# Adafruit_Metro_ESP32-S2_rev_C.net
KiCad netlist of a schematic drawn in EAGLE
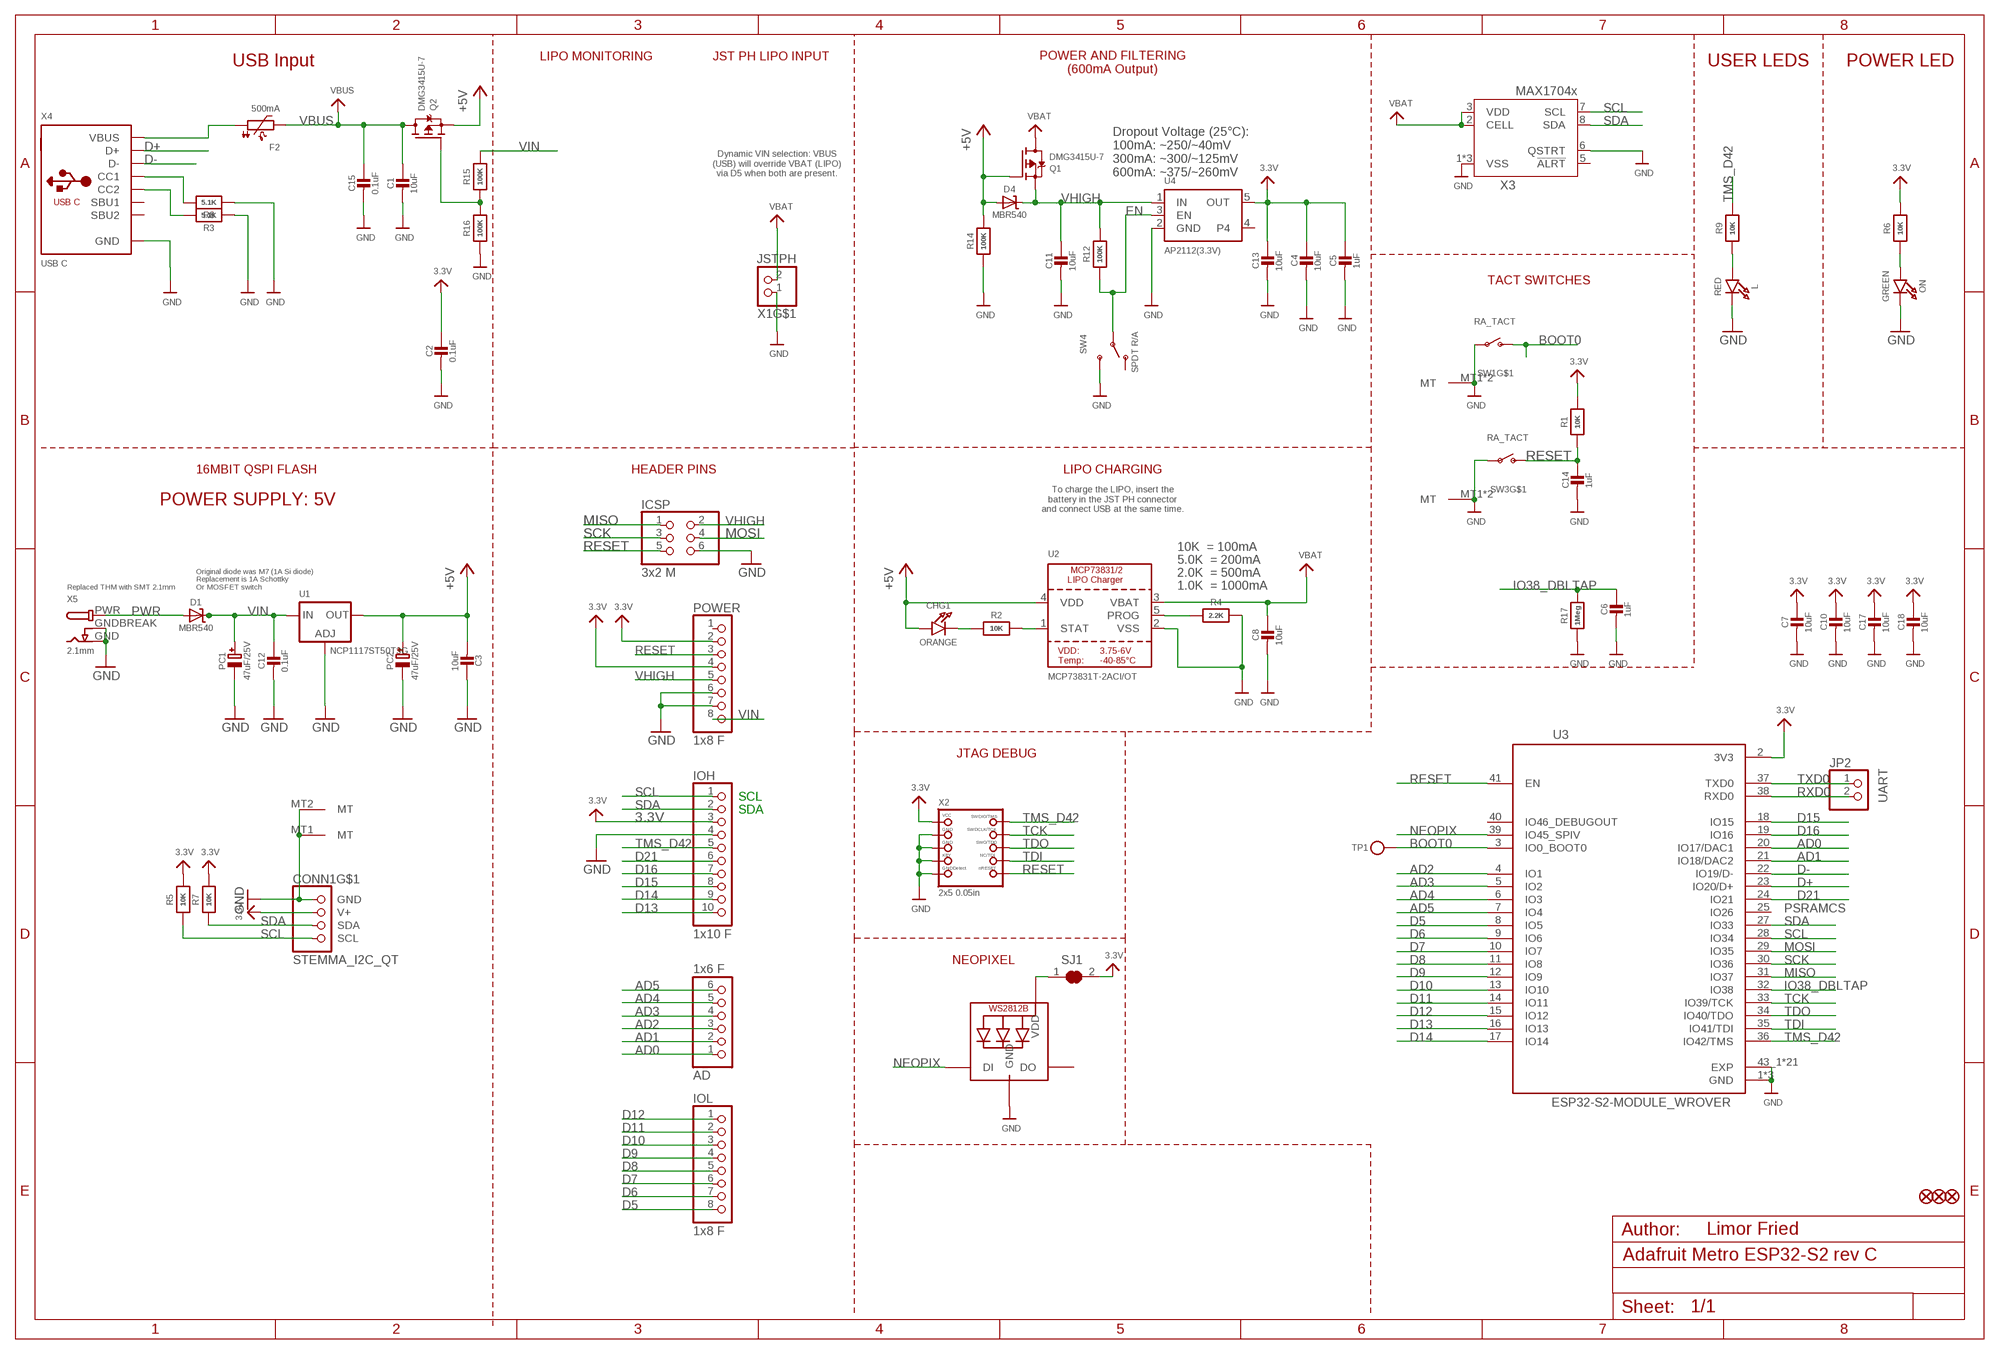
[diagram p0: schematic, sheet 1]

(export (version "E")
  (design (tool "Eeschema 10.0.6"))
  (components
    (comp (ref "AD")
      (value "1x6 F")
      (footprint "eagle-import:1X06_OVALWAVE")
      (libsource (lib "eagle-import") (part "HEADER-1X6OVALWAVE"))
    )
    (comp (ref "C1")
      (value "10uF")
      (footprint "eagle-import:0805-NO")
      (libsource (lib "eagle-import") (part "CAP_CERAMIC0805-NOOUTLINE"))
    )
    (comp (ref "C2")
      (value "0.1uF")
      (footprint "eagle-import:0603-NO")
      (libsource (lib "eagle-import") (part "CAP_CERAMIC0603_NO"))
    )
    (comp (ref "C3")
      (value "10uF")
      (footprint "eagle-import:0805-NO")
      (libsource (lib "eagle-import") (part "CAP_CERAMIC0805-NOOUTLINE"))
    )
    (comp (ref "C4")
      (value "10uF")
      (footprint "eagle-import:0805-NO")
      (libsource (lib "eagle-import") (part "CAP_CERAMIC0805-NOOUTLINE"))
    )
    (comp (ref "C5")
      (value "1uF")
      (footprint "eagle-import:0603-NO")
      (libsource (lib "eagle-import") (part "CAP_CERAMIC0603_NO"))
    )
    (comp (ref "C6")
      (value "1uF")
      (footprint "eagle-import:0603-NO")
      (libsource (lib "eagle-import") (part "CAP_CERAMIC0603_NO"))
    )
    (comp (ref "C7")
      (value "10uF")
      (footprint "eagle-import:0805-NO")
      (libsource (lib "eagle-import") (part "CAP_CERAMIC0805-NOOUTLINE"))
    )
    (comp (ref "C8")
      (value "10uF")
      (footprint "eagle-import:0805-NO")
      (libsource (lib "eagle-import") (part "CAP_CERAMIC0805-NOOUTLINE"))
    )
    (comp (ref "C10")
      (value "10uF")
      (footprint "eagle-import:0805-NO")
      (libsource (lib "eagle-import") (part "CAP_CERAMIC0805-NOOUTLINE"))
    )
    (comp (ref "C11")
      (value "10uF")
      (footprint "eagle-import:0805-NO")
      (libsource (lib "eagle-import") (part "CAP_CERAMIC0805-NOOUTLINE"))
    )
    (comp (ref "C12")
      (value "0.1uF")
      (footprint "eagle-import:0603-NO")
      (libsource (lib "eagle-import") (part "CAP_CERAMIC0603_NO"))
    )
    (comp (ref "C13")
      (value "10uF")
      (footprint "eagle-import:0805-NO")
      (libsource (lib "eagle-import") (part "CAP_CERAMIC0805-NOOUTLINE"))
    )
    (comp (ref "C14")
      (value "1uF")
      (footprint "eagle-import:0603-NO")
      (libsource (lib "eagle-import") (part "CAP_CERAMIC0603_NO"))
    )
    (comp (ref "C15")
      (value "0.1uF")
      (footprint "eagle-import:0603-NO")
      (libsource (lib "eagle-import") (part "CAP_CERAMIC0603_NO"))
    )
    (comp (ref "C17")
      (value "10uF")
      (footprint "eagle-import:0805-NO")
      (libsource (lib "eagle-import") (part "CAP_CERAMIC0805-NOOUTLINE"))
    )
    (comp (ref "C18")
      (value "10uF")
      (footprint "eagle-import:0805-NO")
      (libsource (lib "eagle-import") (part "CAP_CERAMIC0805-NOOUTLINE"))
    )
    (comp (ref "CHG1")
      (value "ORANGE")
      (footprint "eagle-import:CHIPLED_0603_NOOUTLINE")
      (libsource (lib "eagle-import") (part "LED0603_NOOUTLINE"))
    )
    (comp (ref "CONN1")
      (value "STEMMA_I2C_QT")
      (footprint "eagle-import:JST_SH4")
      (libsource (lib "eagle-import") (part "STEMMA_I2C_QT"))
    )
    (comp (ref "D1")
      (value "MBR540")
      (footprint "eagle-import:SOD-123")
      (libsource (lib "eagle-import") (part "DIODE-SCHOTTKYSOD-123"))
    )
    (comp (ref "D4")
      (value "MBR540")
      (footprint "eagle-import:SOD-123")
      (libsource (lib "eagle-import") (part "DIODE-SCHOTTKYSOD-123"))
    )
    (comp (ref "F2")
      (value "500mA")
      (footprint "eagle-import:1206")
      (libsource (lib "eagle-import") (part "PTC1206"))
    )
    (comp (ref "FD1")
      (value "FIDUCIAL_1MM")
      (footprint "eagle-import:FIDUCIAL_1MM")
      (libsource (lib "eagle-import") (part "FIDUCIAL_1MM"))
    )
    (comp (ref "FD2")
      (value "FIDUCIAL_1MM")
      (footprint "eagle-import:FIDUCIAL_1MM")
      (libsource (lib "eagle-import") (part "FIDUCIAL_1MM"))
    )
    (comp (ref "FD3")
      (value "FIDUCIAL_1MM")
      (footprint "eagle-import:FIDUCIAL_1MM")
      (libsource (lib "eagle-import") (part "FIDUCIAL_1MM"))
    )
    (comp (ref "ICSP")
      (value "3x2 M")
      (footprint "eagle-import:2X03_ROUND_70MIL")
      (libsource (lib "eagle-import") (part "HEADER-2X3"))
    )
    (comp (ref "IOH")
      (value "1x10 F")
      (footprint "eagle-import:1X10_OVALWAVE")
      (libsource (lib "eagle-import") (part "HEADER-1X10OVALWAVE"))
    )
    (comp (ref "IOL")
      (value "1x8 F")
      (footprint "eagle-import:1X08_OVALWAVE")
      (libsource (lib "eagle-import") (part "HEADER-1X8OVALWAVE"))
    )
    (comp (ref "JP2")
      (value "UART")
      (footprint "eagle-import:1X02_ROUND")
      (libsource (lib "eagle-import") (part "HEADER-1X2ROUND"))
    )
    (comp (ref "L")
      (value "RED")
      (footprint "eagle-import:CHIPLED_0603_NOOUTLINE")
      (libsource (lib "eagle-import") (part "LED0603_NOOUTLINE"))
    )
    (comp (ref "LED1")
      (value "WS2812B_3535FULL")
      (footprint "eagle-import:LED3535_FULLPADS")
      (libsource (lib "eagle-import") (part "WS2812B_3535FULL"))
    )
    (comp (ref "ON")
      (value "GREEN")
      (footprint "eagle-import:CHIPLED_0603_NOOUTLINE")
      (libsource (lib "eagle-import") (part "LED0603_NOOUTLINE"))
    )
    (comp (ref "PC1")
      (value "47uF/25V")
      (footprint "eagle-import:PANASONIC_D")
      (libsource (lib "eagle-import") (part "CAP_ELECTROLYTICPANASONIC_D"))
    )
    (comp (ref "PC2")
      (value "47uF/25V")
      (footprint "eagle-import:PANASONIC_D")
      (libsource (lib "eagle-import") (part "CAP_ELECTROLYTICPANASONIC_D"))
    )
    (comp (ref "POWER")
      (value "1x8 F")
      (footprint "eagle-import:1X08_OVALWAVE")
      (libsource (lib "eagle-import") (part "HEADER-1X8OVALWAVE"))
    )
    (comp (ref "Q1")
      (value "DMG3415U-7")
      (footprint "eagle-import:SOT23-R")
      (libsource (lib "eagle-import") (part "MOSFET-P"))
    )
    (comp (ref "Q2")
      (value "DMG3415U-7")
      (footprint "eagle-import:SOT23-R")
      (libsource (lib "eagle-import") (part "MOSFET-P"))
    )
    (comp (ref "R1")
      (value "10K")
      (footprint "eagle-import:0603-NO")
      (libsource (lib "eagle-import") (part "RESISTOR_0603_NOOUT"))
    )
    (comp (ref "R2")
      (value "10K")
      (footprint "eagle-import:0603-NO")
      (libsource (lib "eagle-import") (part "RESISTOR_0603_NOOUT"))
    )
    (comp (ref "R3")
      (value "5.1K")
      (footprint "eagle-import:0603-NO")
      (libsource (lib "eagle-import") (part "RESISTOR_0603_NOOUT"))
    )
    (comp (ref "R4")
      (value "2.2K")
      (footprint "eagle-import:0603-NO")
      (libsource (lib "eagle-import") (part "RESISTOR_0603_NOOUT"))
    )
    (comp (ref "R5")
      (value "10K")
      (footprint "eagle-import:0603-NO")
      (libsource (lib "eagle-import") (part "RESISTOR_0603_NOOUT"))
    )
    (comp (ref "R6")
      (value "10K")
      (footprint "eagle-import:0603-NO")
      (libsource (lib "eagle-import") (part "RESISTOR_0603_NOOUT"))
    )
    (comp (ref "R7")
      (value "10K")
      (footprint "eagle-import:0603-NO")
      (libsource (lib "eagle-import") (part "RESISTOR_0603_NOOUT"))
    )
    (comp (ref "R8")
      (value "5.1K")
      (footprint "eagle-import:0603-NO")
      (libsource (lib "eagle-import") (part "RESISTOR_0603_NOOUT"))
    )
    (comp (ref "R9")
      (value "10K")
      (footprint "eagle-import:0603-NO")
      (libsource (lib "eagle-import") (part "RESISTOR_0603_NOOUT"))
    )
    (comp (ref "R12")
      (value "100K")
      (footprint "eagle-import:0603-NO")
      (libsource (lib "eagle-import") (part "RESISTOR_0603_NOOUT"))
    )
    (comp (ref "R14")
      (value "100K")
      (footprint "eagle-import:0603-NO")
      (libsource (lib "eagle-import") (part "RESISTOR_0603_NOOUT"))
    )
    (comp (ref "R15")
      (value "100K")
      (footprint "eagle-import:0603-NO")
      (libsource (lib "eagle-import") (part "RESISTOR_0603_NOOUT"))
    )
    (comp (ref "R16")
      (value "100K")
      (footprint "eagle-import:0603-NO")
      (libsource (lib "eagle-import") (part "RESISTOR_0603_NOOUT"))
    )
    (comp (ref "R17")
      (value "1Meg")
      (footprint "eagle-import:0603-NO")
      (libsource (lib "eagle-import") (part "RESISTOR_0603_NOOUT"))
    )
    (comp (ref "SJ1")
      (value "SOLDERJUMPER_CLOSED")
      (footprint "eagle-import:SOLDERJUMPER_CLOSEDWIRE")
      (libsource (lib "eagle-import") (part "SOLDERJUMPER_CLOSED"))
    )
    (comp (ref "SW1")
      (value "RA_TACT")
      (footprint "eagle-import:SPST_TACTILE_RA")
      (libsource (lib "eagle-import") (part "SWITCH_SPST_MNT_TACT_RA"))
    )
    (comp (ref "SW3")
      (value "RA_TACT")
      (footprint "eagle-import:SPST_TACTILE_RA")
      (libsource (lib "eagle-import") (part "SWITCH_SPST_MNT_TACT_RA"))
    )
    (comp (ref "SW4")
      (value "SPDT R/A")
      (footprint "eagle-import:SPDT_SMT_SSSS811101")
      (libsource (lib "eagle-import") (part "SWITCH_SPDT"))
    )
    (comp (ref "TP1")
      (value "TESTPOINTROUND1.5MMNO")
      (footprint "eagle-import:TESTPOINT_ROUND_1.5MM_NO")
      (libsource (lib "eagle-import") (part "TESTPOINTROUND1.5MMNO"))
    )
    (comp (ref "U1")
      (value "NCP1117ST50T3G")
      (footprint "eagle-import:SOT223-R")
      (libsource (lib "eagle-import") (part "LM1117SOT223-REFLOW"))
    )
    (comp (ref "U2")
      (value "MCP73831T-2ACI/OT")
      (footprint "eagle-import:SOT23-5")
      (libsource (lib "eagle-import") (part "MCP73831/2"))
    )
    (comp (ref "U3")
      (value "ESP32-S2-MODULE_WROVER")
      (footprint "eagle-import:MODULE_ESP32-S2-WROVER")
      (fields (field (name "MF") "Espressif Systems") (field (name "MP") "ESP32-S2-WROVER"))
      (libsource (lib "eagle-import") (part "ESP32-S2-MODULE_WROVER"))
    )
    (comp (ref "U4")
      (value "AP2112(3.3V)")
      (footprint "eagle-import:SOT23-5")
      (fields (field (name "JLC_ROTATION") "0"))
      (libsource (lib "eagle-import") (part "VREG_SOT23-5"))
    )
    (comp (ref "X1")
      (value "JSTPH")
      (footprint "eagle-import:JSTPH2_BATT")
      (libsource (lib "eagle-import") (part "CON_JST_PH_2PIN_MT_BATT"))
    )
    (comp (ref "X2")
      (value "2x5 0.05in")
      (footprint "eagle-import:2X05_1.27MM_BOX_POSTS")
      (libsource (lib "eagle-import") (part "JTAG-CORTEXBOXPOSTS"))
    )
    (comp (ref "X3")
      (value "MAX17048/T")
      (footprint "eagle-import:TDFN8_2X2MM")
      (libsource (lib "eagle-import") (part "MAX17048/T"))
    )
    (comp (ref "X4")
      (value "USB C")
      (footprint "eagle-import:USB_C_CUSB31-CFM2AX-01-X")
      (libsource (lib "eagle-import") (part "USB_C"))
    )
    (comp (ref "X5")
      (value "2.1mm")
      (footprint "eagle-import:DCJACK_2MM_PTH")
      (libsource (lib "eagle-import") (part "DCBARRELPTH"))
    )
  )
  (nets
    (net (code "1") (name "+5V") (class "Default")
      (node (ref "C3") (pin "2") (pinfunction "2_2") (pintype "passive"))
      (node (ref "CHG1") (pin "A") (pinfunction "A_A") (pintype "passive"))
      (node (ref "D4") (pin "A") (pinfunction "A_A") (pintype "passive"))
      (node (ref "PC2") (pin "+") (pinfunction "+_+") (pintype "passive"))
      (node (ref "Q1") (pin "1") (pinfunction "G_1") (pintype "passive"))
      (node (ref "Q2") (pin "2") (pinfunction "S_2") (pintype "passive"))
      (node (ref "R14") (pin "2") (pinfunction "2_2") (pintype "passive"))
      (node (ref "U1") (pin "2") (pinfunction "OUT_2") (pintype "passive"))
      (node (ref "U1") (pin "4") (pinfunction "OUT_4") (pintype "passive"))
      (node (ref "U2") (pin "4") (pinfunction "VDD_4") (pintype "power_in"))
    )
    (net (code "2") (name "/AD0") (class "Default")
      (node (ref "AD") (pin "1") (pinfunction "1_1") (pintype "passive"))
      (node (ref "U3") (pin "20") (pinfunction "IO17/DAC1_20") (pintype "bidirectional"))
    )
    (net (code "3") (name "/AD1") (class "Default")
      (node (ref "AD") (pin "2") (pinfunction "2_2") (pintype "passive"))
      (node (ref "U3") (pin "21") (pinfunction "IO18/DAC2_21") (pintype "bidirectional"))
    )
    (net (code "4") (name "/AD2") (class "Default")
      (node (ref "AD") (pin "3") (pinfunction "3_3") (pintype "passive"))
      (node (ref "U3") (pin "4") (pinfunction "IO1_4") (pintype "bidirectional"))
    )
    (net (code "5") (name "/AD3") (class "Default")
      (node (ref "AD") (pin "4") (pinfunction "4_4") (pintype "passive"))
      (node (ref "U3") (pin "5") (pinfunction "IO2_5") (pintype "bidirectional"))
    )
    (net (code "6") (name "/AD4") (class "Default")
      (node (ref "AD") (pin "5") (pinfunction "5_5") (pintype "passive"))
      (node (ref "U3") (pin "6") (pinfunction "IO3_6") (pintype "bidirectional"))
    )
    (net (code "7") (name "/AD5") (class "Default")
      (node (ref "AD") (pin "6") (pinfunction "6_6") (pintype "passive"))
      (node (ref "U3") (pin "7") (pinfunction "IO4_7") (pintype "bidirectional"))
    )
    (net (code "8") (name "/BOOT0") (class "Default")
      (node (ref "SW1") (pin "2") (pinfunction "S_2") (pintype "passive"))
      (node (ref "TP1") (pin "P$1") (pinfunction "P$1_P$1") (pintype "bidirectional"))
      (node (ref "U3") (pin "3") (pinfunction "IO0_BOOT0_3") (pintype "bidirectional"))
    )
    (net (code "9") (name "/D+") (class "Default")
      (node (ref "U3") (pin "23") (pinfunction "IO20/D+_23") (pintype "bidirectional"))
      (node (ref "X4") (pin "A6") (pinfunction "D+_A6") (pintype "bidirectional"))
      (node (ref "X4") (pin "B6") (pinfunction "D+_B6") (pintype "bidirectional"))
    )
    (net (code "10") (name "/D-") (class "Default")
      (node (ref "U3") (pin "22") (pinfunction "IO19/D-_22") (pintype "bidirectional"))
      (node (ref "X4") (pin "A7") (pinfunction "D-_A7") (pintype "bidirectional"))
      (node (ref "X4") (pin "B7") (pinfunction "D-_B7") (pintype "bidirectional"))
    )
    (net (code "11") (name "/D5") (class "Default")
      (node (ref "IOL") (pin "8") (pinfunction "8_8") (pintype "passive"))
      (node (ref "U3") (pin "8") (pinfunction "IO5_8") (pintype "bidirectional"))
    )
    (net (code "12") (name "/D6") (class "Default")
      (node (ref "IOL") (pin "7") (pinfunction "7_7") (pintype "passive"))
      (node (ref "U3") (pin "9") (pinfunction "IO6_9") (pintype "bidirectional"))
    )
    (net (code "13") (name "/D7") (class "Default")
      (node (ref "IOL") (pin "6") (pinfunction "6_6") (pintype "passive"))
      (node (ref "U3") (pin "10") (pinfunction "IO7_10") (pintype "bidirectional"))
    )
    (net (code "14") (name "/D8") (class "Default")
      (node (ref "IOL") (pin "5") (pinfunction "5_5") (pintype "passive"))
      (node (ref "U3") (pin "11") (pinfunction "IO8_11") (pintype "bidirectional"))
    )
    (net (code "15") (name "/D9") (class "Default")
      (node (ref "IOL") (pin "4") (pinfunction "4_4") (pintype "passive"))
      (node (ref "U3") (pin "12") (pinfunction "IO9_12") (pintype "bidirectional"))
    )
    (net (code "16") (name "/D10") (class "Default")
      (node (ref "IOL") (pin "3") (pinfunction "3_3") (pintype "passive"))
      (node (ref "U3") (pin "13") (pinfunction "IO10_13") (pintype "bidirectional"))
    )
    (net (code "17") (name "/D11") (class "Default")
      (node (ref "IOL") (pin "2") (pinfunction "2_2") (pintype "passive"))
      (node (ref "U3") (pin "14") (pinfunction "IO11_14") (pintype "bidirectional"))
    )
    (net (code "18") (name "/D12") (class "Default")
      (node (ref "IOL") (pin "1") (pinfunction "1_1") (pintype "passive"))
      (node (ref "U3") (pin "15") (pinfunction "IO12_15") (pintype "bidirectional"))
    )
    (net (code "19") (name "/D13") (class "Default")
      (node (ref "IOH") (pin "10") (pinfunction "10_10") (pintype "passive"))
      (node (ref "U3") (pin "16") (pinfunction "IO13_16") (pintype "bidirectional"))
    )
    (net (code "20") (name "/D14") (class "Default")
      (node (ref "IOH") (pin "9") (pinfunction "9_9") (pintype "passive"))
      (node (ref "U3") (pin "17") (pinfunction "IO14_17") (pintype "bidirectional"))
    )
    (net (code "21") (name "/D15") (class "Default")
      (node (ref "IOH") (pin "8") (pinfunction "8_8") (pintype "passive"))
      (node (ref "U3") (pin "18") (pinfunction "IO15_18") (pintype "bidirectional"))
    )
    (net (code "22") (name "/D16") (class "Default")
      (node (ref "IOH") (pin "7") (pinfunction "7_7") (pintype "passive"))
      (node (ref "U3") (pin "19") (pinfunction "IO16_19") (pintype "bidirectional"))
    )
    (net (code "23") (name "/D21") (class "Default")
      (node (ref "IOH") (pin "6") (pinfunction "6_6") (pintype "passive"))
      (node (ref "U3") (pin "24") (pinfunction "IO21_24") (pintype "bidirectional"))
    )
    (net (code "24") (name "/EN") (class "Default")
      (node (ref "R12") (pin "1") (pinfunction "1_1") (pintype "passive"))
      (node (ref "SW4") (pin "B") (pinfunction "P_B") (pintype "passive"))
      (node (ref "U4") (pin "3") (pinfunction "EN_3") (pintype "input"))
    )
    (net (code "25") (name "/IO38_DBLTAP") (class "Default")
      (node (ref "C6") (pin "1") (pinfunction "1_1") (pintype "passive"))
      (node (ref "R17") (pin "2") (pinfunction "2_2") (pintype "passive"))
      (node (ref "U3") (pin "32") (pinfunction "IO38_32") (pintype "bidirectional"))
    )
    (net (code "26") (name "/MISO") (class "Default")
      (node (ref "ICSP") (pin "1") (pinfunction "1_1") (pintype "passive"))
      (node (ref "U3") (pin "31") (pinfunction "IO37_31") (pintype "bidirectional"))
    )
    (net (code "27") (name "/MOSI") (class "Default")
      (node (ref "ICSP") (pin "4") (pinfunction "4_4") (pintype "passive"))
      (node (ref "U3") (pin "29") (pinfunction "IO35_29") (pintype "input"))
    )
    (net (code "28") (name "/NEOPIX") (class "Default")
      (node (ref "LED1") (pin "1") (pinfunction "DI_1") (pintype "input"))
      (node (ref "U3") (pin "39") (pinfunction "IO45_SPIV_39") (pintype "bidirectional"))
    )
    (net (code "29") (name "/PWR") (class "Default")
      (node (ref "D1") (pin "A") (pinfunction "A_A") (pintype "passive"))
      (node (ref "X5") (pin "PWR") (pinfunction "PWR_PWR") (pintype "power_in"))
    )
    (net (code "30") (name "/RESET") (class "Default")
      (node (ref "C14") (pin "1") (pinfunction "1_1") (pintype "passive"))
      (node (ref "ICSP") (pin "5") (pinfunction "5_5") (pintype "passive"))
      (node (ref "POWER") (pin "3") (pinfunction "3_3") (pintype "passive"))
      (node (ref "R1") (pin "1") (pinfunction "1_1") (pintype "passive"))
      (node (ref "SW3") (pin "2") (pinfunction "S_2") (pintype "passive"))
      (node (ref "U3") (pin "41") (pinfunction "EN_41") (pintype "input"))
      (node (ref "X2") (pin "10") (pinfunction "NRESET_10") (pintype "bidirectional"))
    )
    (net (code "31") (name "/RXD0") (class "Default")
      (node (ref "JP2") (pin "2") (pinfunction "2_2") (pintype "passive"))
      (node (ref "U3") (pin "38") (pinfunction "RXD0_38") (pintype "bidirectional"))
    )
    (net (code "32") (name "/SCK") (class "Default")
      (node (ref "ICSP") (pin "3") (pinfunction "3_3") (pintype "passive"))
      (node (ref "U3") (pin "30") (pinfunction "IO36_30") (pintype "bidirectional"))
    )
    (net (code "33") (name "/SCL") (class "Default")
      (node (ref "CONN1") (pin "4") (pinfunction "SCL_4") (pintype "passive"))
      (node (ref "IOH") (pin "1") (pinfunction "1_1") (pintype "passive"))
      (node (ref "R5") (pin "1") (pinfunction "1_1") (pintype "passive"))
      (node (ref "U3") (pin "28") (pinfunction "IO34_28") (pintype "input"))
      (node (ref "X3") (pin "7") (pinfunction "SCL_7") (pintype "bidirectional"))
    )
    (net (code "34") (name "/SDA") (class "Default")
      (node (ref "CONN1") (pin "3") (pinfunction "SDA_3") (pintype "passive"))
      (node (ref "IOH") (pin "2") (pinfunction "2_2") (pintype "passive"))
      (node (ref "R7") (pin "1") (pinfunction "1_1") (pintype "passive"))
      (node (ref "U3") (pin "27") (pinfunction "IO33_27") (pintype "bidirectional"))
      (node (ref "X3") (pin "8") (pinfunction "SDA_8") (pintype "bidirectional"))
    )
    (net (code "35") (name "/TCK") (class "Default")
      (node (ref "U3") (pin "33") (pinfunction "IO39/TCK_33") (pintype "bidirectional"))
      (node (ref "X2") (pin "4") (pinfunction "SWDCLK_4") (pintype "bidirectional"))
    )
    (net (code "36") (name "/TDI") (class "Default")
      (node (ref "U3") (pin "35") (pinfunction "IO41/TDI_35") (pintype "bidirectional"))
      (node (ref "X2") (pin "8") (pinfunction "TDI_8") (pintype "bidirectional"))
    )
    (net (code "37") (name "/TDO") (class "Default")
      (node (ref "U3") (pin "34") (pinfunction "IO40/TDO_34") (pintype "bidirectional"))
      (node (ref "X2") (pin "6") (pinfunction "SWO_6") (pintype "bidirectional"))
    )
    (net (code "38") (name "/TMS_D42") (class "Default")
      (node (ref "IOH") (pin "5") (pinfunction "5_5") (pintype "passive"))
      (node (ref "R9") (pin "2") (pinfunction "2_2") (pintype "passive"))
      (node (ref "U3") (pin "36") (pinfunction "IO42/TMS_36") (pintype "bidirectional"))
      (node (ref "X2") (pin "2") (pinfunction "SWDIO_2") (pintype "bidirectional"))
    )
    (net (code "39") (name "/TXD0") (class "Default")
      (node (ref "JP2") (pin "1") (pinfunction "1_1") (pintype "passive"))
      (node (ref "U3") (pin "37") (pinfunction "TXD0_37") (pintype "bidirectional"))
    )
    (net (code "40") (name "/VHIGH") (class "Default")
      (node (ref "C11") (pin "1") (pinfunction "1_1") (pintype "passive"))
      (node (ref "D4") (pin "C") (pinfunction "C_C") (pintype "passive"))
      (node (ref "ICSP") (pin "2") (pinfunction "2_2") (pintype "passive"))
      (node (ref "POWER") (pin "5") (pinfunction "5_5") (pintype "passive"))
      (node (ref "Q1") (pin "2") (pinfunction "S_2") (pintype "passive"))
      (node (ref "R12") (pin "2") (pinfunction "2_2") (pintype "passive"))
      (node (ref "U4") (pin "1") (pinfunction "IN_1") (pintype "power_in"))
    )
    (net (code "41") (name "/VIN") (class "Default")
      (node (ref "C12") (pin "1") (pinfunction "1_1") (pintype "passive"))
      (node (ref "D1") (pin "C") (pinfunction "C_C") (pintype "passive"))
      (node (ref "PC1") (pin "+") (pinfunction "+_+") (pintype "passive"))
      (node (ref "POWER") (pin "8") (pinfunction "8_8") (pintype "passive"))
      (node (ref "R15") (pin "2") (pinfunction "2_2") (pintype "passive"))
      (node (ref "U1") (pin "3") (pinfunction "IN_3") (pintype "input"))
    )
    (net (code "42") (name "3.3V") (class "Default")
      (node (ref "C10") (pin "1") (pinfunction "1_1") (pintype "passive"))
      (node (ref "C13") (pin "1") (pinfunction "1_1") (pintype "passive"))
      (node (ref "C17") (pin "1") (pinfunction "1_1") (pintype "passive"))
      (node (ref "C18") (pin "1") (pinfunction "1_1") (pintype "passive"))
      (node (ref "C2") (pin "1") (pinfunction "1_1") (pintype "passive"))
      (node (ref "C4") (pin "1") (pinfunction "1_1") (pintype "passive"))
      (node (ref "C5") (pin "1") (pinfunction "1_1") (pintype "passive"))
      (node (ref "C7") (pin "1") (pinfunction "1_1") (pintype "passive"))
      (node (ref "CONN1") (pin "2") (pinfunction "V+_2") (pintype "passive"))
      (node (ref "IOH") (pin "3") (pinfunction "3_3") (pintype "passive"))
      (node (ref "POWER") (pin "2") (pinfunction "2_2") (pintype "passive"))
      (node (ref "POWER") (pin "4") (pinfunction "4_4") (pintype "passive"))
      (node (ref "R1") (pin "2") (pinfunction "2_2") (pintype "passive"))
      (node (ref "R5") (pin "2") (pinfunction "2_2") (pintype "passive"))
      (node (ref "R6") (pin "2") (pinfunction "2_2") (pintype "passive"))
      (node (ref "R7") (pin "2") (pinfunction "2_2") (pintype "passive"))
      (node (ref "SJ1") (pin "2") (pinfunction "2_2") (pintype "passive"))
      (node (ref "U3") (pin "2") (pinfunction "3V3_2") (pintype "power_in"))
      (node (ref "U4") (pin "5") (pinfunction "OUT_5") (pintype "power_in"))
      (node (ref "X2") (pin "1") (pinfunction "VCC_1") (pintype "power_in"))
    )
    (net (code "43") (name "GND") (class "Default")
      (node (ref "C1") (pin "2") (pinfunction "2_2") (pintype "passive"))
      (node (ref "C10") (pin "2") (pinfunction "2_2") (pintype "passive"))
      (node (ref "C11") (pin "2") (pinfunction "2_2") (pintype "passive"))
      (node (ref "C12") (pin "2") (pinfunction "2_2") (pintype "passive"))
      (node (ref "C13") (pin "2") (pinfunction "2_2") (pintype "passive"))
      (node (ref "C14") (pin "2") (pinfunction "2_2") (pintype "passive"))
      (node (ref "C15") (pin "2") (pinfunction "2_2") (pintype "passive"))
      (node (ref "C17") (pin "2") (pinfunction "2_2") (pintype "passive"))
      (node (ref "C18") (pin "2") (pinfunction "2_2") (pintype "passive"))
      (node (ref "C2") (pin "2") (pinfunction "2_2") (pintype "passive"))
      (node (ref "C3") (pin "1") (pinfunction "1_1") (pintype "passive"))
      (node (ref "C4") (pin "2") (pinfunction "2_2") (pintype "passive"))
      (node (ref "C5") (pin "2") (pinfunction "2_2") (pintype "passive"))
      (node (ref "C6") (pin "2") (pinfunction "2_2") (pintype "passive"))
      (node (ref "C7") (pin "2") (pinfunction "2_2") (pintype "passive"))
      (node (ref "C8") (pin "2") (pinfunction "2_2") (pintype "passive"))
      (node (ref "CONN1") (pin "1") (pinfunction "GND_1") (pintype "passive"))
      (node (ref "CONN1") (pin "MT1") (pinfunction "MT_MT1") (pintype "bidirectional"))
      (node (ref "CONN1") (pin "MT2") (pinfunction "MT_MT2") (pintype "bidirectional"))
      (node (ref "ICSP") (pin "6") (pinfunction "6_6") (pintype "passive"))
      (node (ref "IOH") (pin "4") (pinfunction "4_4") (pintype "passive"))
      (node (ref "L") (pin "C") (pinfunction "C_C") (pintype "passive"))
      (node (ref "LED1") (pin "4") (pinfunction "GND_4") (pintype "power_in"))
      (node (ref "ON") (pin "C") (pinfunction "C_C") (pintype "passive"))
      (node (ref "PC1") (pin "-") (pinfunction "-_-") (pintype "passive"))
      (node (ref "PC2") (pin "-") (pinfunction "-_-") (pintype "passive"))
      (node (ref "POWER") (pin "6") (pinfunction "6_6") (pintype "passive"))
      (node (ref "POWER") (pin "7") (pinfunction "7_7") (pintype "passive"))
      (node (ref "R14") (pin "1") (pinfunction "1_1") (pintype "passive"))
      (node (ref "R16") (pin "1") (pinfunction "1_1") (pintype "passive"))
      (node (ref "R17") (pin "1") (pinfunction "1_1") (pintype "passive"))
      (node (ref "R3") (pin "1") (pinfunction "1_1") (pintype "passive"))
      (node (ref "R4") (pin "2") (pinfunction "2_2") (pintype "passive"))
      (node (ref "R8") (pin "1") (pinfunction "1_1") (pintype "passive"))
      (node (ref "SW1") (pin "1") (pinfunction "P_1") (pintype "passive"))
      (node (ref "SW1") (pin "MT1") (pinfunction "MT_MT1") (pintype "bidirectional"))
      (node (ref "SW1") (pin "MT2") (pinfunction "MT_MT2") (pintype "bidirectional"))
      (node (ref "SW3") (pin "1") (pinfunction "P_1") (pintype "passive"))
      (node (ref "SW3") (pin "MT1") (pinfunction "MT_MT1") (pintype "bidirectional"))
      (node (ref "SW3") (pin "MT2") (pinfunction "MT_MT2") (pintype "bidirectional"))
      (node (ref "SW4") (pin "C") (pinfunction "S_C") (pintype "passive"))
      (node (ref "U1") (pin "1") (pinfunction "ADJ_1") (pintype "input"))
      (node (ref "U2") (pin "2") (pinfunction "VSS_2") (pintype "power_in"))
      (node (ref "U3") (pin "1") (pinfunction "GND_1") (pintype "power_in"))
      (node (ref "U3") (pin "26") (pinfunction "GND_26") (pintype "power_in"))
      (node (ref "U3") (pin "42") (pinfunction "GND_42") (pintype "power_in"))
      (node (ref "U3") (pin "43_1") (pinfunction "EXP_43_1") (pintype "power_in"))
      (node (ref "U3") (pin "43_10") (pinfunction "EXP_43_10") (pintype "power_in"))
      (node (ref "U3") (pin "43_11") (pinfunction "EXP_43_11") (pintype "power_in"))
      (node (ref "U3") (pin "43_12") (pinfunction "EXP_43_12") (pintype "power_in"))
      (node (ref "U3") (pin "43_13") (pinfunction "EXP_43_13") (pintype "power_in"))
      (node (ref "U3") (pin "43_14") (pinfunction "EXP_43_14") (pintype "power_in"))
      (node (ref "U3") (pin "43_15") (pinfunction "EXP_43_15") (pintype "power_in"))
      (node (ref "U3") (pin "43_16") (pinfunction "EXP_43_16") (pintype "power_in"))
      (node (ref "U3") (pin "43_17") (pinfunction "EXP_43_17") (pintype "power_in"))
      (node (ref "U3") (pin "43_18") (pinfunction "EXP_43_18") (pintype "power_in"))
      (node (ref "U3") (pin "43_19") (pinfunction "EXP_43_19") (pintype "power_in"))
      (node (ref "U3") (pin "43_2") (pinfunction "EXP_43_2") (pintype "power_in"))
      (node (ref "U3") (pin "43_20") (pinfunction "EXP_43_20") (pintype "power_in"))
      (node (ref "U3") (pin "43_21") (pinfunction "EXP_43_21") (pintype "power_in"))
      (node (ref "U3") (pin "43_3") (pinfunction "EXP_43_3") (pintype "power_in"))
      (node (ref "U3") (pin "43_4") (pinfunction "EXP_43_4") (pintype "power_in"))
      (node (ref "U3") (pin "43_5") (pinfunction "EXP_43_5") (pintype "power_in"))
      (node (ref "U3") (pin "43_6") (pinfunction "EXP_43_6") (pintype "power_in"))
      (node (ref "U3") (pin "43_7") (pinfunction "EXP_43_7") (pintype "power_in"))
      (node (ref "U3") (pin "43_8") (pinfunction "EXP_43_8") (pintype "power_in"))
      (node (ref "U3") (pin "43_9") (pinfunction "EXP_43_9") (pintype "power_in"))
      (node (ref "U4") (pin "2") (pinfunction "GND_2") (pintype "power_in"))
      (node (ref "X1") (pin "1") (pinfunction "1_1") (pintype "passive"))
      (node (ref "X2") (pin "3") (pinfunction "GND_3") (pintype "power_in"))
      (node (ref "X2") (pin "5") (pinfunction "GND_5") (pintype "power_in"))
      (node (ref "X2") (pin "7") (pinfunction "KEY_7") (pintype "bidirectional"))
      (node (ref "X2") (pin "9") (pinfunction "GNDDETECT_9") (pintype "bidirectional"))
      (node (ref "X3") (pin "1") (pinfunction "VSS_1") (pintype "power_in"))
      (node (ref "X3") (pin "4") (pinfunction "VSS_4") (pintype "power_in"))
      (node (ref "X3") (pin "6") (pinfunction "QSTRT_6") (pintype "input"))
      (node (ref "X3") (pin "THERMAL") (pinfunction "VSS_THERMAL") (pintype "power_in"))
      (node (ref "X4") (pin "A1B12") (pinfunction "GND_A1B12") (pintype "power_in"))
      (node (ref "X4") (pin "B1A12") (pinfunction "GND_B1A12") (pintype "power_in"))
      (node (ref "X5") (pin "GND") (pinfunction "GND_GND") (pintype "power_in"))
      (node (ref "X5") (pin "GNDBREAK") (pinfunction "GNDBREAK_GNDBREAK") (pintype "power_in"))
    )
    (net (code "44") (name "Net-(CHG1-PadC)") (class "Default")
      (node (ref "CHG1") (pin "C") (pinfunction "C_C") (pintype "passive"))
      (node (ref "R2") (pin "1") (pinfunction "1_1") (pintype "passive"))
    )
    (net (code "45") (name "Net-(F2-Pad1)") (class "Default")
      (node (ref "F2") (pin "1") (pinfunction "1_1") (pintype "passive"))
      (node (ref "X4") (pin "A4B9") (pinfunction "VBUS_A4B9") (pintype "power_in"))
      (node (ref "X4") (pin "B4A9") (pinfunction "VBUS_B4A9") (pintype "power_in"))
    )
    (net (code "46") (name "Net-(L-PadA)") (class "Default")
      (node (ref "L") (pin "A") (pinfunction "A_A") (pintype "passive"))
      (node (ref "R9") (pin "1") (pinfunction "1_1") (pintype "passive"))
    )
    (net (code "47") (name "Net-(LED1-VDD)") (class "Default")
      (node (ref "LED1") (pin "2") (pinfunction "VDD_2") (pintype "power_in"))
      (node (ref "SJ1") (pin "1") (pinfunction "1_1") (pintype "passive"))
    )
    (net (code "48") (name "Net-(ON-PadA)") (class "Default")
      (node (ref "ON") (pin "A") (pinfunction "A_A") (pintype "passive"))
      (node (ref "R6") (pin "1") (pinfunction "1_1") (pintype "passive"))
    )
    (net (code "49") (name "Net-(Q2-G)") (class "Default")
      (node (ref "Q2") (pin "1") (pinfunction "G_1") (pintype "passive"))
      (node (ref "R15") (pin "1") (pinfunction "1_1") (pintype "passive"))
      (node (ref "R16") (pin "2") (pinfunction "2_2") (pintype "passive"))
    )
    (net (code "50") (name "Net-(U2-PROG)") (class "Default")
      (node (ref "R4") (pin "1") (pinfunction "1_1") (pintype "passive"))
      (node (ref "U2") (pin "5") (pinfunction "PROG_5") (pintype "input"))
    )
    (net (code "51") (name "Net-(U2-STAT)") (class "Default")
      (node (ref "R2") (pin "2") (pinfunction "2_2") (pintype "passive"))
      (node (ref "U2") (pin "1") (pinfunction "STAT_1") (pintype "output"))
    )
    (net (code "52") (name "Net-(X4-CC1)") (class "Default")
      (node (ref "R8") (pin "2") (pinfunction "2_2") (pintype "passive"))
      (node (ref "X4") (pin "A5") (pinfunction "CC1_A5") (pintype "bidirectional"))
    )
    (net (code "53") (name "Net-(X4-CC2)") (class "Default")
      (node (ref "R3") (pin "2") (pinfunction "2_2") (pintype "passive"))
      (node (ref "X4") (pin "B5") (pinfunction "CC2_B5") (pintype "bidirectional"))
    )
    (net (code "54") (name "VBAT") (class "Default")
      (node (ref "C8") (pin "1") (pinfunction "1_1") (pintype "passive"))
      (node (ref "Q1") (pin "3") (pinfunction "D_3") (pintype "passive"))
      (node (ref "U2") (pin "3") (pinfunction "VBAT_3") (pintype "power_in"))
      (node (ref "X1") (pin "2") (pinfunction "2_2") (pintype "passive"))
      (node (ref "X3") (pin "2") (pinfunction "CELL_2") (pintype "power_in"))
      (node (ref "X3") (pin "3") (pinfunction "VDD_3") (pintype "power_in"))
    )
    (net (code "55") (name "VBUS") (class "Default")
      (node (ref "C1") (pin "1") (pinfunction "1_1") (pintype "passive"))
      (node (ref "C15") (pin "1") (pinfunction "1_1") (pintype "passive"))
      (node (ref "F2") (pin "2") (pinfunction "2_2") (pintype "passive"))
      (node (ref "Q2") (pin "3") (pinfunction "D_3") (pintype "passive"))
    )
    (net (code "56") (name "unconnected-(LED1-DO-Pad3)") (class "Default")
      (node (ref "LED1") (pin "3") (pinfunction "DO_3") (pintype "output"))
    )
    (net (code "57") (name "unconnected-(POWER-Pad1)") (class "Default")
      (node (ref "POWER") (pin "1") (pinfunction "1_1") (pintype "passive"))
    )
    (net (code "58") (name "unconnected-(SW4-O-PadA)") (class "Default")
      (node (ref "SW4") (pin "A") (pinfunction "O_A") (pintype "passive"))
    )
    (net (code "59") (name "unconnected-(U3-IO26-Pad25)") (class "Default")
      (node (ref "U3") (pin "25") (pinfunction "IO26_25") (pintype "bidirectional"))
    )
    (net (code "60") (name "unconnected-(U3-IO46_DEBUGOUT-Pad40)") (class "Default")
      (node (ref "U3") (pin "40") (pinfunction "IO46_DEBUGOUT_40") (pintype "input"))
    )
    (net (code "61") (name "unconnected-(U4-P4-Pad4)") (class "Default")
      (node (ref "U4") (pin "4") (pinfunction "P4_4") (pintype "bidirectional"))
    )
    (net (code "62") (name "unconnected-(X3-~{ALRT}-Pad5)") (class "Default")
      (node (ref "X3") (pin "5") (pinfunction "~{ALRT}_5") (pintype "output"))
    )
    (net (code "63") (name "unconnected-(X4-SBU1-PadA8)") (class "Default")
      (node (ref "X4") (pin "A8") (pinfunction "SBU1_A8") (pintype "bidirectional"))
    )
    (net (code "64") (name "unconnected-(X4-SBU2-PadB8)") (class "Default")
      (node (ref "X4") (pin "B8") (pinfunction "SBU2_B8") (pintype "bidirectional"))
    )
  )
)
